# music_bord.net
KiCad netlist of a schematic drawn in EAGLE
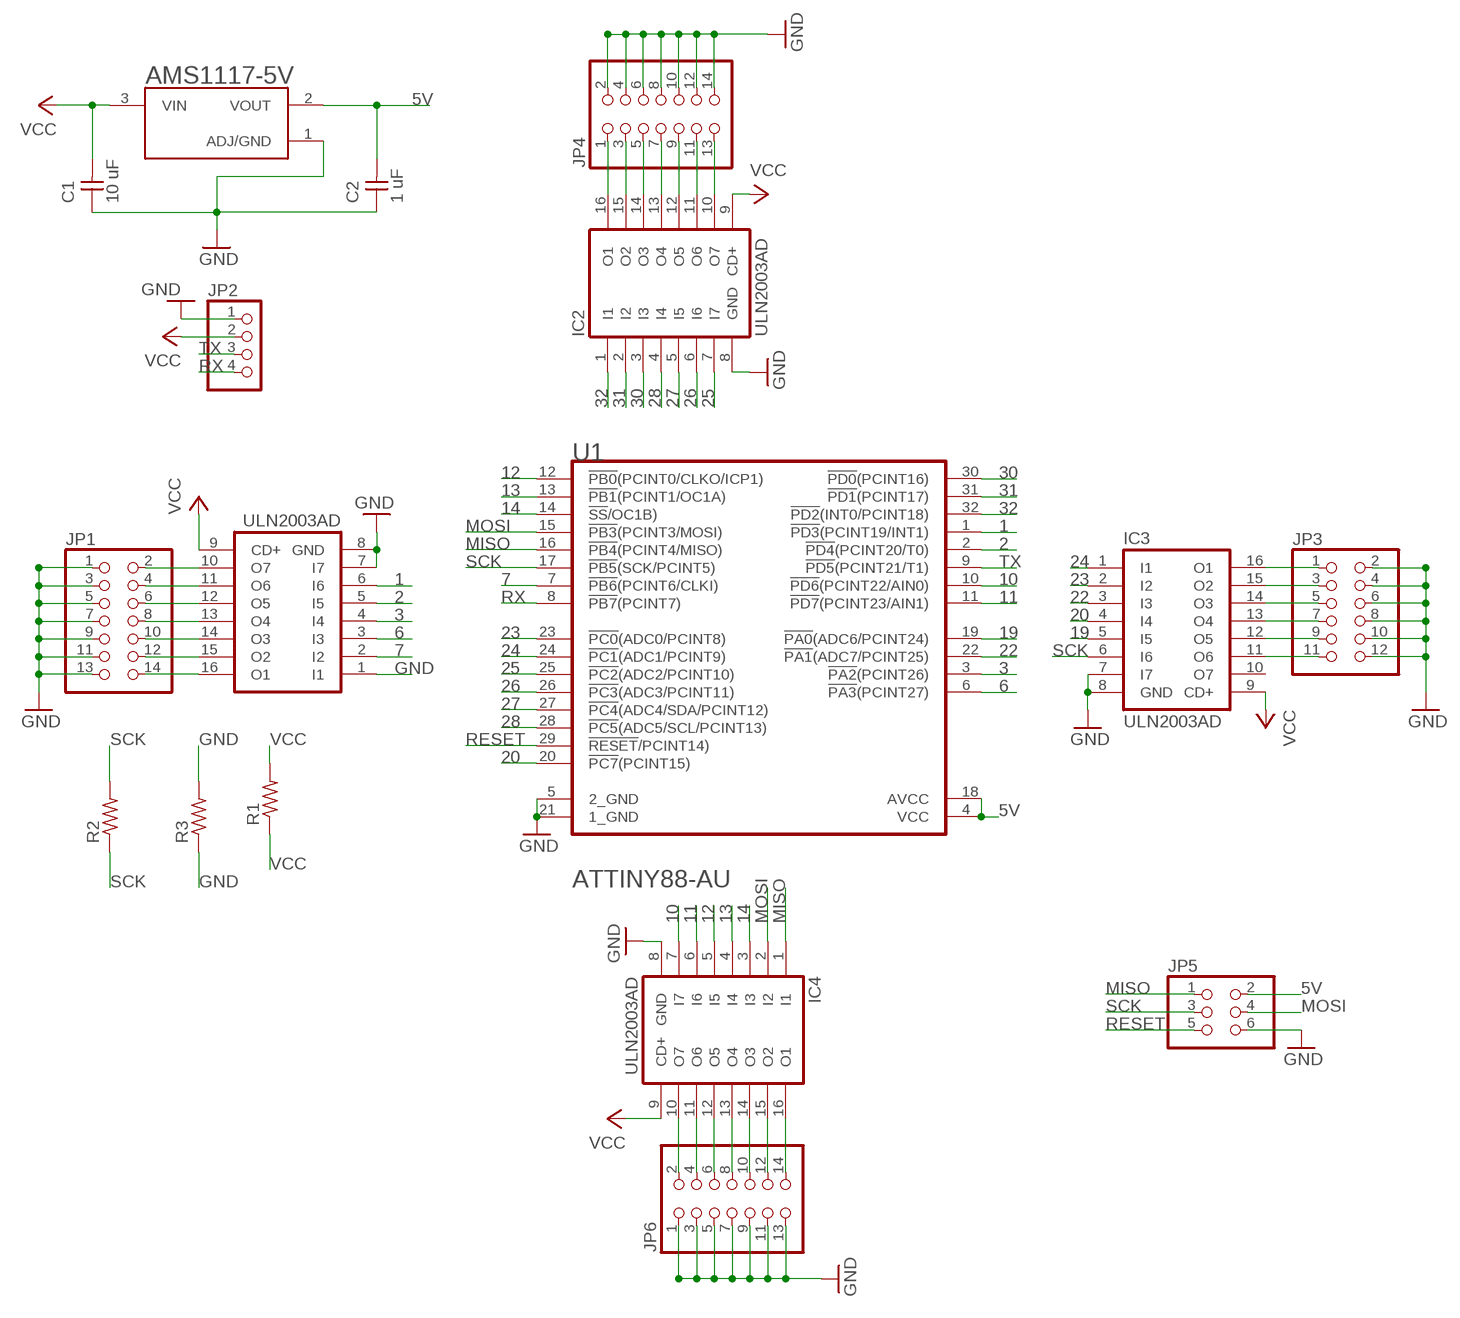
[diagram p0: schematic, sheet 1]

(export (version "E")
  (design (tool "Eeschema 10.0.6"))
  (components
    (comp (ref "AMS1117-5V")
      (value "AMS1117-3.3")
      (footprint "eagle-import:SOT229P700X180-4N")
      (fields (field (name "MF") "Advanced Monolithic Systems"))
      (libsource (lib "eagle-import") (part "AMS1117-3.3"))
    )
    (comp (ref "C1")
      (value "10 uF")
      (footprint "eagle-import:C1206FAB")
      (libsource (lib "eagle-import") (part "CAP_UNPOLARIZEDFAB"))
    )
    (comp (ref "C2")
      (value "1 uF")
      (footprint "eagle-import:C1206FAB")
      (libsource (lib "eagle-import") (part "CAP_UNPOLARIZEDFAB"))
    )
    (comp (ref "IC1")
      (value "ULN2003AD")
      (footprint "eagle-import:SO16")
      (libsource (lib "eagle-import") (part "ULN2003AD"))
    )
    (comp (ref "IC2")
      (value "ULN2003AD")
      (footprint "eagle-import:SO16")
      (libsource (lib "eagle-import") (part "ULN2003AD"))
    )
    (comp (ref "IC3")
      (value "ULN2003AD")
      (footprint "eagle-import:SO16")
      (libsource (lib "eagle-import") (part "ULN2003AD"))
    )
    (comp (ref "IC4")
      (value "ULN2003AD")
      (footprint "eagle-import:SO16")
      (libsource (lib "eagle-import") (part "ULN2003AD"))
    )
    (comp (ref "JP1")
      (value "PINHD-2X7SMT")
      (footprint "eagle-import:2X07_SMT")
      (libsource (lib "eagle-import") (part "PINHD-2X7SMT"))
    )
    (comp (ref "JP2")
      (value "PINHD-1X4/90")
      (footprint "eagle-import:1X04_90")
      (libsource (lib "eagle-import") (part "PINHD-1X4/90"))
    )
    (comp (ref "JP3")
      (value "PINHD-2X6SMT")
      (footprint "eagle-import:2X06_SMT")
      (libsource (lib "eagle-import") (part "PINHD-2X6SMT"))
    )
    (comp (ref "JP4")
      (value "PINHD-2X7SMT")
      (footprint "eagle-import:2X07_SMT")
      (libsource (lib "eagle-import") (part "PINHD-2X7SMT"))
    )
    (comp (ref "JP5")
      (value "CONN_03X2-PINHEAD-SMD")
      (footprint "eagle-import:2X03SMD")
      (libsource (lib "eagle-import") (part "CONN_03X2-PINHEAD-SMD"))
    )
    (comp (ref "JP6")
      (value "PINHD-2X7SMT")
      (footprint "eagle-import:2X07_SMT")
      (libsource (lib "eagle-import") (part "PINHD-2X7SMT"))
    )
    (comp (ref "R1")
      (value "R1206FAB")
      (footprint "eagle-import:R1206FAB")
      (libsource (lib "eagle-import") (part "R1206FAB"))
    )
    (comp (ref "R2")
      (value "R1206FAB")
      (footprint "eagle-import:R1206FAB")
      (libsource (lib "eagle-import") (part "R1206FAB"))
    )
    (comp (ref "R3")
      (value "R1206FAB")
      (footprint "eagle-import:R1206FAB")
      (libsource (lib "eagle-import") (part "R1206FAB"))
    )
    (comp (ref "U1")
      (value "MICROCHIP_-_ATMEL_ATTINY88-AUMICROCHIP_-_ATMEL_ATTINY88-AU_0_0")
      (footprint "eagle-import:MICROCHIP_-_ATMEL_ATTINY88-AU_0")
      (fields (field (name "MF") "Microchip / Atmel") (field (name "MPN") "ATTINY88-AU"))
      (libsource (lib "eagle-import") (part "MICROCHIP_-_ATMEL_ATTINY88-AUMICROCHIP_-_ATMEL_ATTINY88-AU_0_0"))
    )
  )
  (nets
    (net (code "1") (name "/1") (class "Default")
      (node (ref "IC1") (pin "6") (pinfunction "I6_6") (pintype "input"))
      (node (ref "U1") (pin "1") (pinfunction "~{PD3}(PCINT19/INT1)_1") (pintype "bidirectional"))
    )
    (net (code "2") (name "/2") (class "Default")
      (node (ref "IC1") (pin "5") (pinfunction "I5_5") (pintype "input"))
      (node (ref "U1") (pin "2") (pinfunction "~{PD4}(PCINT20/T0)_2") (pintype "bidirectional"))
    )
    (net (code "3") (name "/3") (class "Default")
      (node (ref "IC1") (pin "4") (pinfunction "I4_4") (pintype "input"))
      (node (ref "U1") (pin "3") (pinfunction "~{PA2}(PCINT26)_3") (pintype "bidirectional"))
    )
    (net (code "4") (name "/5V") (class "Default")
      (node (ref "AMS1117-5V") (pin "2") (pinfunction "VOUT_2") (pintype "output"))
      (node (ref "C2") (pin "2") (pinfunction "2_2") (pintype "passive"))
      (node (ref "JP5") (pin "2") (pinfunction "2_2") (pintype "passive"))
      (node (ref "U1") (pin "18") (pinfunction "AVCC_18") (pintype "power_in"))
      (node (ref "U1") (pin "4") (pinfunction "VCC_4") (pintype "power_in"))
    )
    (net (code "5") (name "/6") (class "Default")
      (node (ref "IC1") (pin "3") (pinfunction "I3_3") (pintype "input"))
      (node (ref "U1") (pin "6") (pinfunction "~{PA3}(PCINT27)_6") (pintype "bidirectional"))
    )
    (net (code "6") (name "/7") (class "Default")
      (node (ref "IC1") (pin "2") (pinfunction "I2_2") (pintype "input"))
      (node (ref "U1") (pin "7") (pinfunction "~{PB6}(PCINT6/CLKI)_7") (pintype "bidirectional"))
    )
    (net (code "7") (name "/10") (class "Default")
      (node (ref "IC4") (pin "7") (pinfunction "I7_7") (pintype "input"))
      (node (ref "U1") (pin "10") (pinfunction "~{PD6}(PCINT22/AIN0)_10") (pintype "bidirectional"))
    )
    (net (code "8") (name "/11") (class "Default")
      (node (ref "IC4") (pin "6") (pinfunction "I6_6") (pintype "input"))
      (node (ref "U1") (pin "11") (pinfunction "~{PD7}(PCINT23/AIN1)_11") (pintype "bidirectional"))
    )
    (net (code "9") (name "/12") (class "Default")
      (node (ref "IC4") (pin "5") (pinfunction "I5_5") (pintype "input"))
      (node (ref "U1") (pin "12") (pinfunction "~{PB0}(PCINT0/CLKO/ICP1)_12") (pintype "bidirectional"))
    )
    (net (code "10") (name "/13") (class "Default")
      (node (ref "IC4") (pin "4") (pinfunction "I4_4") (pintype "input"))
      (node (ref "U1") (pin "13") (pinfunction "~{PB1}(PCINT1/OC1A)_13") (pintype "bidirectional"))
    )
    (net (code "11") (name "/14") (class "Default")
      (node (ref "IC4") (pin "3") (pinfunction "I3_3") (pintype "input"))
      (node (ref "U1") (pin "14") (pinfunction "~{SS}/OC1B)_14") (pintype "bidirectional"))
    )
    (net (code "12") (name "/19") (class "Default")
      (node (ref "IC3") (pin "5") (pinfunction "I5_5") (pintype "input"))
      (node (ref "U1") (pin "19") (pinfunction "~{PA0}(ADC6/PCINT24)_19") (pintype "bidirectional"))
    )
    (net (code "13") (name "/20") (class "Default")
      (node (ref "IC3") (pin "4") (pinfunction "I4_4") (pintype "input"))
      (node (ref "U1") (pin "20") (pinfunction "~{PC7}(PCINT15)_20") (pintype "bidirectional"))
    )
    (net (code "14") (name "/22") (class "Default")
      (node (ref "IC3") (pin "3") (pinfunction "I3_3") (pintype "input"))
      (node (ref "U1") (pin "22") (pinfunction "~{PA1}(ADC7/PCINT25)_22") (pintype "bidirectional"))
    )
    (net (code "15") (name "/23") (class "Default")
      (node (ref "IC3") (pin "2") (pinfunction "I2_2") (pintype "input"))
      (node (ref "U1") (pin "23") (pinfunction "~{PC0}(ADC0/PCINT8)_23") (pintype "bidirectional"))
    )
    (net (code "16") (name "/24") (class "Default")
      (node (ref "IC3") (pin "1") (pinfunction "I1_1") (pintype "input"))
      (node (ref "U1") (pin "24") (pinfunction "~{PC1}(ADC1/PCINT9)_24") (pintype "bidirectional"))
    )
    (net (code "17") (name "/25") (class "Default")
      (node (ref "IC2") (pin "7") (pinfunction "I7_7") (pintype "input"))
      (node (ref "U1") (pin "25") (pinfunction "~{PC2}(ADC2/PCINT10)_25") (pintype "bidirectional"))
    )
    (net (code "18") (name "/26") (class "Default")
      (node (ref "IC2") (pin "6") (pinfunction "I6_6") (pintype "input"))
      (node (ref "U1") (pin "26") (pinfunction "~{PC3}(ADC3/PCINT11)_26") (pintype "bidirectional"))
    )
    (net (code "19") (name "/27") (class "Default")
      (node (ref "IC2") (pin "5") (pinfunction "I5_5") (pintype "input"))
      (node (ref "U1") (pin "27") (pinfunction "~{PC4}(ADC4/SDA/PCINT12)_27") (pintype "bidirectional"))
    )
    (net (code "20") (name "/28") (class "Default")
      (node (ref "IC2") (pin "4") (pinfunction "I4_4") (pintype "input"))
      (node (ref "U1") (pin "28") (pinfunction "~{PC5}(ADC5/SCL/PCINT13)_28") (pintype "bidirectional"))
    )
    (net (code "21") (name "/30") (class "Default")
      (node (ref "IC2") (pin "3") (pinfunction "I3_3") (pintype "input"))
      (node (ref "U1") (pin "30") (pinfunction "~{PD0}(PCINT16)_30") (pintype "bidirectional"))
    )
    (net (code "22") (name "/31") (class "Default")
      (node (ref "IC2") (pin "2") (pinfunction "I2_2") (pintype "input"))
      (node (ref "U1") (pin "31") (pinfunction "~{PD1}(PCINT17)_31") (pintype "bidirectional"))
    )
    (net (code "23") (name "/32") (class "Default")
      (node (ref "IC2") (pin "1") (pinfunction "I1_1") (pintype "input"))
      (node (ref "U1") (pin "32") (pinfunction "~{PD2}(INT0/PCINT18)_32") (pintype "bidirectional"))
    )
    (net (code "24") (name "/MISO") (class "Default")
      (node (ref "IC4") (pin "1") (pinfunction "I1_1") (pintype "input"))
      (node (ref "JP5") (pin "1") (pinfunction "1_1") (pintype "passive"))
      (node (ref "U1") (pin "16") (pinfunction "~{PB4}(PCINT4/MISO)_16") (pintype "bidirectional"))
    )
    (net (code "25") (name "/MOSI") (class "Default")
      (node (ref "IC4") (pin "2") (pinfunction "I2_2") (pintype "input"))
      (node (ref "JP5") (pin "4") (pinfunction "4_4") (pintype "passive"))
      (node (ref "U1") (pin "15") (pinfunction "~{PB3}(PCINT3/MOSI)_15") (pintype "bidirectional"))
    )
    (net (code "26") (name "/RESET") (class "Default")
      (node (ref "JP5") (pin "5") (pinfunction "5_5") (pintype "passive"))
      (node (ref "U1") (pin "29") (pinfunction "~{RESET}/PCINT14)_29") (pintype "bidirectional"))
    )
    (net (code "27") (name "/RX") (class "Default")
      (node (ref "JP2") (pin "4") (pinfunction "4_4") (pintype "passive"))
      (node (ref "U1") (pin "8") (pinfunction "~{PB7}(PCINT7)_8") (pintype "bidirectional"))
    )
    (net (code "28") (name "/SCK") (class "Default")
      (node (ref "IC3") (pin "6") (pinfunction "I6_6") (pintype "input"))
      (node (ref "JP5") (pin "3") (pinfunction "3_3") (pintype "passive"))
      (node (ref "R2") (pin "1") (pinfunction "1_1") (pintype "passive"))
      (node (ref "R2") (pin "2") (pinfunction "2_2") (pintype "passive"))
      (node (ref "U1") (pin "17") (pinfunction "~{PB5}(SCK/PCINT5)_17") (pintype "bidirectional"))
    )
    (net (code "29") (name "/TX") (class "Default")
      (node (ref "JP2") (pin "3") (pinfunction "3_3") (pintype "passive"))
      (node (ref "U1") (pin "9") (pinfunction "~{PD5}(PCINT21/T1)_9") (pintype "bidirectional"))
    )
    (net (code "30") (name "GND") (class "Default")
      (node (ref "AMS1117-5V") (pin "1") (pinfunction "ADJ/GND_1") (pintype "power_in"))
      (node (ref "C1") (pin "1") (pinfunction "1_1") (pintype "passive"))
      (node (ref "C2") (pin "1") (pinfunction "1_1") (pintype "passive"))
      (node (ref "IC1") (pin "1") (pinfunction "I1_1") (pintype "input"))
      (node (ref "IC1") (pin "7") (pinfunction "I7_7") (pintype "input"))
      (node (ref "IC1") (pin "8") (pinfunction "GND_8") (pintype "power_in"))
      (node (ref "IC2") (pin "8") (pinfunction "GND_8") (pintype "power_in"))
      (node (ref "IC3") (pin "7") (pinfunction "I7_7") (pintype "input"))
      (node (ref "IC3") (pin "8") (pinfunction "GND_8") (pintype "power_in"))
      (node (ref "IC4") (pin "8") (pinfunction "GND_8") (pintype "power_in"))
      (node (ref "JP1") (pin "1") (pinfunction "1_1") (pintype "passive"))
      (node (ref "JP1") (pin "11") (pinfunction "11_11") (pintype "passive"))
      (node (ref "JP1") (pin "13") (pinfunction "13_13") (pintype "passive"))
      (node (ref "JP1") (pin "3") (pinfunction "3_3") (pintype "passive"))
      (node (ref "JP1") (pin "5") (pinfunction "5_5") (pintype "passive"))
      (node (ref "JP1") (pin "7") (pinfunction "7_7") (pintype "passive"))
      (node (ref "JP1") (pin "9") (pinfunction "9_9") (pintype "passive"))
      (node (ref "JP2") (pin "1") (pinfunction "1_1") (pintype "passive"))
      (node (ref "JP3") (pin "10") (pinfunction "10_10") (pintype "passive"))
      (node (ref "JP3") (pin "12") (pinfunction "12_12") (pintype "passive"))
      (node (ref "JP3") (pin "2") (pinfunction "2_2") (pintype "passive"))
      (node (ref "JP3") (pin "4") (pinfunction "4_4") (pintype "passive"))
      (node (ref "JP3") (pin "6") (pinfunction "6_6") (pintype "passive"))
      (node (ref "JP3") (pin "8") (pinfunction "8_8") (pintype "passive"))
      (node (ref "JP4") (pin "10") (pinfunction "10_10") (pintype "passive"))
      (node (ref "JP4") (pin "12") (pinfunction "12_12") (pintype "passive"))
      (node (ref "JP4") (pin "14") (pinfunction "14_14") (pintype "passive"))
      (node (ref "JP4") (pin "2") (pinfunction "2_2") (pintype "passive"))
      (node (ref "JP4") (pin "4") (pinfunction "4_4") (pintype "passive"))
      (node (ref "JP4") (pin "6") (pinfunction "6_6") (pintype "passive"))
      (node (ref "JP4") (pin "8") (pinfunction "8_8") (pintype "passive"))
      (node (ref "JP5") (pin "6") (pinfunction "6_6") (pintype "passive"))
      (node (ref "JP6") (pin "1") (pinfunction "1_1") (pintype "passive"))
      (node (ref "JP6") (pin "11") (pinfunction "11_11") (pintype "passive"))
      (node (ref "JP6") (pin "13") (pinfunction "13_13") (pintype "passive"))
      (node (ref "JP6") (pin "3") (pinfunction "3_3") (pintype "passive"))
      (node (ref "JP6") (pin "5") (pinfunction "5_5") (pintype "passive"))
      (node (ref "JP6") (pin "7") (pinfunction "7_7") (pintype "passive"))
      (node (ref "JP6") (pin "9") (pinfunction "9_9") (pintype "passive"))
      (node (ref "R3") (pin "1") (pinfunction "1_1") (pintype "passive"))
      (node (ref "R3") (pin "2") (pinfunction "2_2") (pintype "passive"))
      (node (ref "U1") (pin "21") (pinfunction "1_GND_21") (pintype "power_in"))
      (node (ref "U1") (pin "5") (pinfunction "2_GND_5") (pintype "power_in"))
    )
    (net (code "31") (name "Net-(IC1-O1)") (class "Default")
      (node (ref "IC1") (pin "16") (pinfunction "O1_16") (pintype "open_collector"))
      (node (ref "JP1") (pin "14") (pinfunction "14_14") (pintype "passive"))
    )
    (net (code "32") (name "Net-(IC1-O2)") (class "Default")
      (node (ref "IC1") (pin "15") (pinfunction "O2_15") (pintype "open_collector"))
      (node (ref "JP1") (pin "12") (pinfunction "12_12") (pintype "passive"))
    )
    (net (code "33") (name "Net-(IC1-O3)") (class "Default")
      (node (ref "IC1") (pin "14") (pinfunction "O3_14") (pintype "open_collector"))
      (node (ref "JP1") (pin "10") (pinfunction "10_10") (pintype "passive"))
    )
    (net (code "34") (name "Net-(IC1-O4)") (class "Default")
      (node (ref "IC1") (pin "13") (pinfunction "O4_13") (pintype "open_collector"))
      (node (ref "JP1") (pin "8") (pinfunction "8_8") (pintype "passive"))
    )
    (net (code "35") (name "Net-(IC1-O5)") (class "Default")
      (node (ref "IC1") (pin "12") (pinfunction "O5_12") (pintype "open_collector"))
      (node (ref "JP1") (pin "6") (pinfunction "6_6") (pintype "passive"))
    )
    (net (code "36") (name "Net-(IC1-O6)") (class "Default")
      (node (ref "IC1") (pin "11") (pinfunction "O6_11") (pintype "open_collector"))
      (node (ref "JP1") (pin "4") (pinfunction "4_4") (pintype "passive"))
    )
    (net (code "37") (name "Net-(IC1-O7)") (class "Default")
      (node (ref "IC1") (pin "10") (pinfunction "O7_10") (pintype "open_collector"))
      (node (ref "JP1") (pin "2") (pinfunction "2_2") (pintype "passive"))
    )
    (net (code "38") (name "Net-(IC2-O1)") (class "Default")
      (node (ref "IC2") (pin "16") (pinfunction "O1_16") (pintype "open_collector"))
      (node (ref "JP4") (pin "1") (pinfunction "1_1") (pintype "passive"))
    )
    (net (code "39") (name "Net-(IC2-O2)") (class "Default")
      (node (ref "IC2") (pin "15") (pinfunction "O2_15") (pintype "open_collector"))
      (node (ref "JP4") (pin "3") (pinfunction "3_3") (pintype "passive"))
    )
    (net (code "40") (name "Net-(IC2-O3)") (class "Default")
      (node (ref "IC2") (pin "14") (pinfunction "O3_14") (pintype "open_collector"))
      (node (ref "JP4") (pin "5") (pinfunction "5_5") (pintype "passive"))
    )
    (net (code "41") (name "Net-(IC2-O4)") (class "Default")
      (node (ref "IC2") (pin "13") (pinfunction "O4_13") (pintype "open_collector"))
      (node (ref "JP4") (pin "7") (pinfunction "7_7") (pintype "passive"))
    )
    (net (code "42") (name "Net-(IC2-O5)") (class "Default")
      (node (ref "IC2") (pin "12") (pinfunction "O5_12") (pintype "open_collector"))
      (node (ref "JP4") (pin "9") (pinfunction "9_9") (pintype "passive"))
    )
    (net (code "43") (name "Net-(IC2-O6)") (class "Default")
      (node (ref "IC2") (pin "11") (pinfunction "O6_11") (pintype "open_collector"))
      (node (ref "JP4") (pin "11") (pinfunction "11_11") (pintype "passive"))
    )
    (net (code "44") (name "Net-(IC2-O7)") (class "Default")
      (node (ref "IC2") (pin "10") (pinfunction "O7_10") (pintype "open_collector"))
      (node (ref "JP4") (pin "13") (pinfunction "13_13") (pintype "passive"))
    )
    (net (code "45") (name "Net-(IC3-O1)") (class "Default")
      (node (ref "IC3") (pin "16") (pinfunction "O1_16") (pintype "open_collector"))
      (node (ref "JP3") (pin "1") (pinfunction "1_1") (pintype "passive"))
    )
    (net (code "46") (name "Net-(IC3-O2)") (class "Default")
      (node (ref "IC3") (pin "15") (pinfunction "O2_15") (pintype "open_collector"))
      (node (ref "JP3") (pin "3") (pinfunction "3_3") (pintype "passive"))
    )
    (net (code "47") (name "Net-(IC3-O3)") (class "Default")
      (node (ref "IC3") (pin "14") (pinfunction "O3_14") (pintype "open_collector"))
      (node (ref "JP3") (pin "5") (pinfunction "5_5") (pintype "passive"))
    )
    (net (code "48") (name "Net-(IC3-O4)") (class "Default")
      (node (ref "IC3") (pin "13") (pinfunction "O4_13") (pintype "open_collector"))
      (node (ref "JP3") (pin "7") (pinfunction "7_7") (pintype "passive"))
    )
    (net (code "49") (name "Net-(IC3-O5)") (class "Default")
      (node (ref "IC3") (pin "12") (pinfunction "O5_12") (pintype "open_collector"))
      (node (ref "JP3") (pin "9") (pinfunction "9_9") (pintype "passive"))
    )
    (net (code "50") (name "Net-(IC3-O6)") (class "Default")
      (node (ref "IC3") (pin "11") (pinfunction "O6_11") (pintype "open_collector"))
      (node (ref "JP3") (pin "11") (pinfunction "11_11") (pintype "passive"))
    )
    (net (code "51") (name "Net-(IC4-O1)") (class "Default")
      (node (ref "IC4") (pin "16") (pinfunction "O1_16") (pintype "open_collector"))
      (node (ref "JP6") (pin "14") (pinfunction "14_14") (pintype "passive"))
    )
    (net (code "52") (name "Net-(IC4-O2)") (class "Default")
      (node (ref "IC4") (pin "15") (pinfunction "O2_15") (pintype "open_collector"))
      (node (ref "JP6") (pin "12") (pinfunction "12_12") (pintype "passive"))
    )
    (net (code "53") (name "Net-(IC4-O3)") (class "Default")
      (node (ref "IC4") (pin "14") (pinfunction "O3_14") (pintype "open_collector"))
      (node (ref "JP6") (pin "10") (pinfunction "10_10") (pintype "passive"))
    )
    (net (code "54") (name "Net-(IC4-O4)") (class "Default")
      (node (ref "IC4") (pin "13") (pinfunction "O4_13") (pintype "open_collector"))
      (node (ref "JP6") (pin "8") (pinfunction "8_8") (pintype "passive"))
    )
    (net (code "55") (name "Net-(IC4-O5)") (class "Default")
      (node (ref "IC4") (pin "12") (pinfunction "O5_12") (pintype "open_collector"))
      (node (ref "JP6") (pin "6") (pinfunction "6_6") (pintype "passive"))
    )
    (net (code "56") (name "Net-(IC4-O6)") (class "Default")
      (node (ref "IC4") (pin "11") (pinfunction "O6_11") (pintype "open_collector"))
      (node (ref "JP6") (pin "4") (pinfunction "4_4") (pintype "passive"))
    )
    (net (code "57") (name "Net-(IC4-O7)") (class "Default")
      (node (ref "IC4") (pin "10") (pinfunction "O7_10") (pintype "open_collector"))
      (node (ref "JP6") (pin "2") (pinfunction "2_2") (pintype "passive"))
    )
    (net (code "58") (name "VCC") (class "Default")
      (node (ref "AMS1117-5V") (pin "3") (pinfunction "VIN_3") (pintype "input"))
      (node (ref "C1") (pin "2") (pinfunction "2_2") (pintype "passive"))
      (node (ref "IC1") (pin "9") (pinfunction "CD+_9") (pintype "passive"))
      (node (ref "IC2") (pin "9") (pinfunction "CD+_9") (pintype "passive"))
      (node (ref "IC3") (pin "9") (pinfunction "CD+_9") (pintype "passive"))
      (node (ref "IC4") (pin "9") (pinfunction "CD+_9") (pintype "passive"))
      (node (ref "JP2") (pin "2") (pinfunction "2_2") (pintype "passive"))
      (node (ref "R1") (pin "1") (pinfunction "1_1") (pintype "passive"))
      (node (ref "R1") (pin "2") (pinfunction "2_2") (pintype "passive"))
    )
    (net (code "59") (name "unconnected-(IC3-O7-Pad10)") (class "Default")
      (node (ref "IC3") (pin "10") (pinfunction "O7_10") (pintype "open_collector"))
    )
  )
)
